# Buzzer_Module.net
KiCad netlist of a schematic drawn in EasyEDA Pro
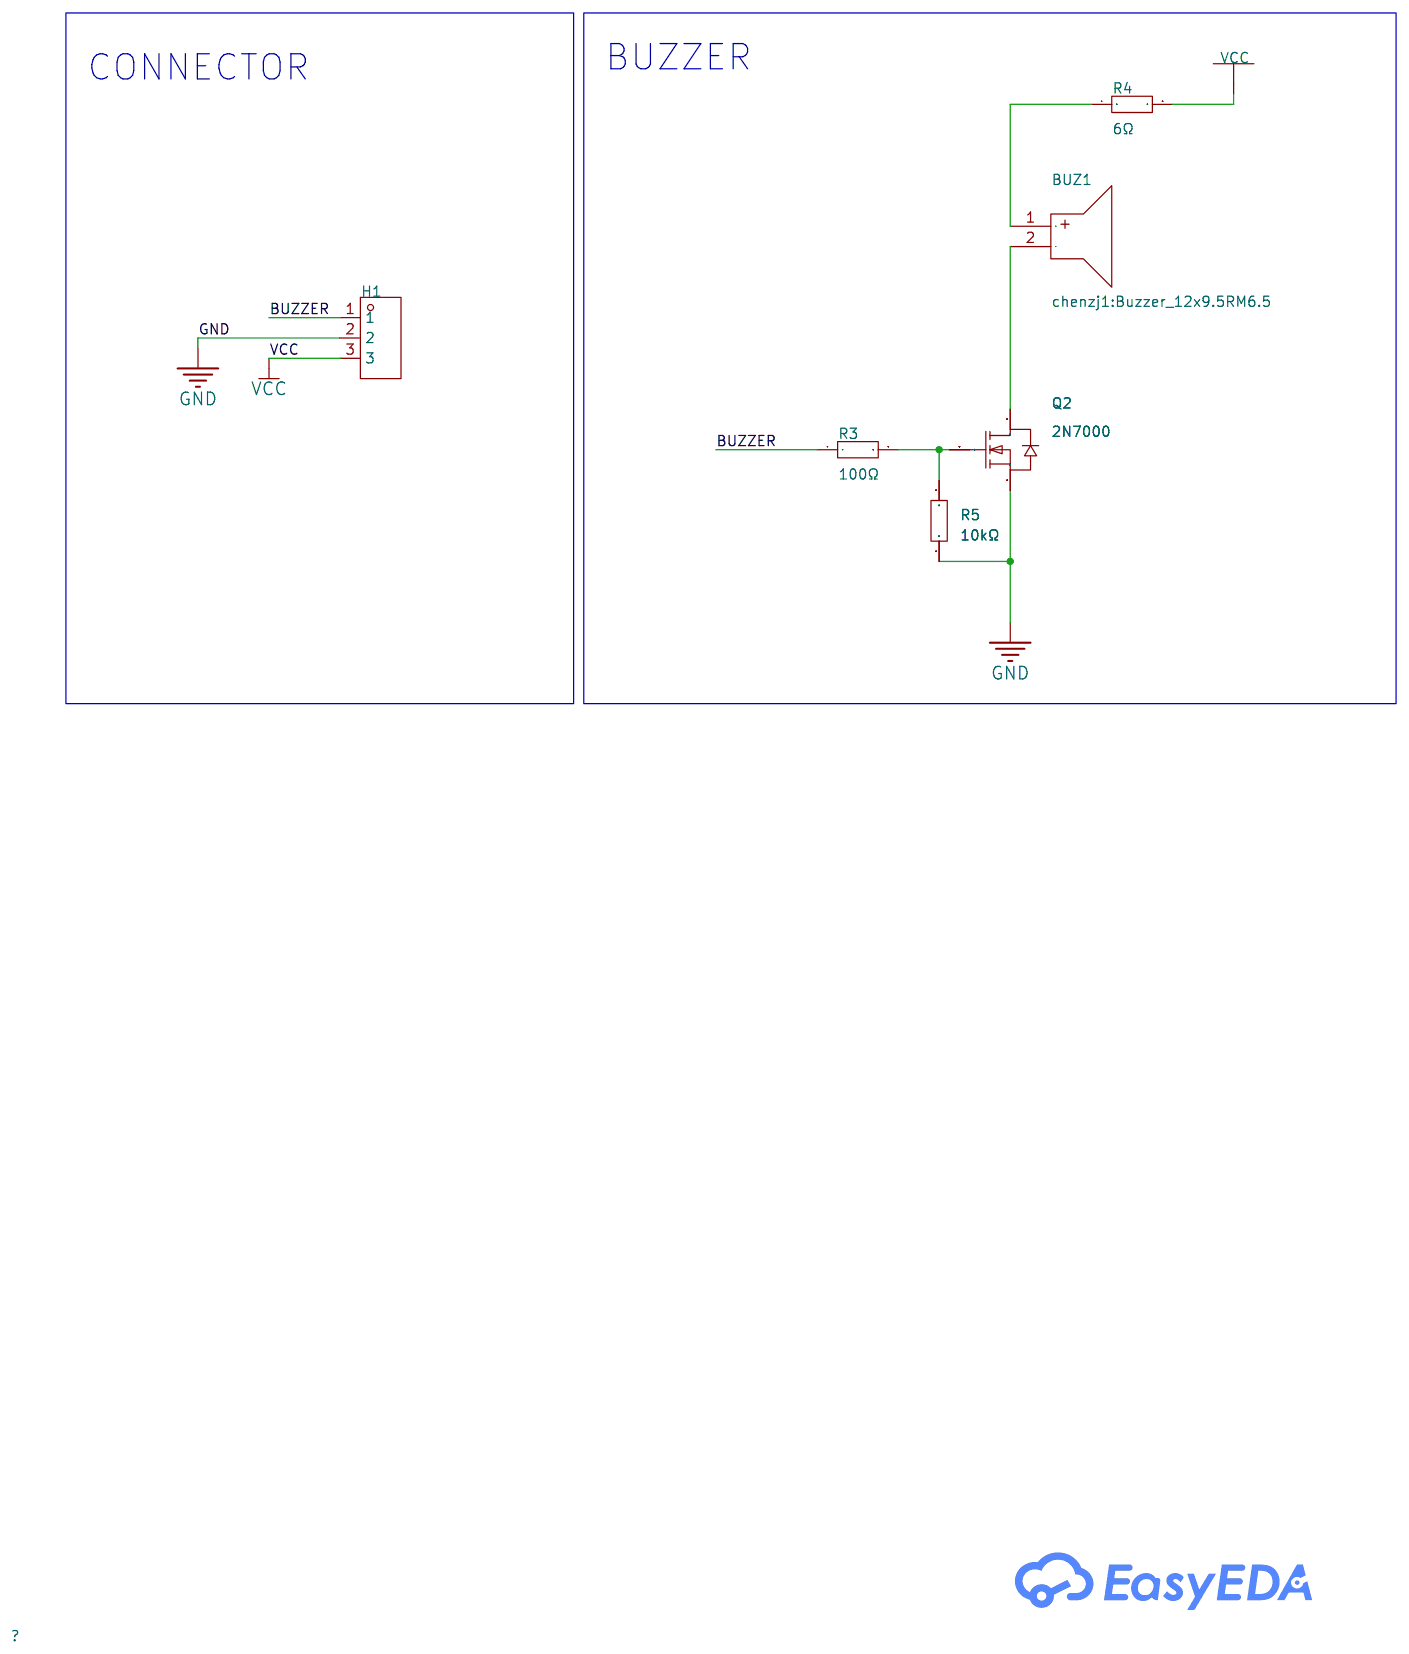
[diagram p0: schematic sheet]

(export (version "E")
  (design (tool "Eeschema 10.0.6"))
  (components
    (comp (ref "BUZ1")
      (value "chenzj1:Buzzer_12x9.5RM6.5")
      (footprint "easyedapro:BUZ-TH_BD12.0-P6.50-D0.6_SEA-1285F")
      (libsource (lib "easyedapro") (part "CHENZJ1{colon}BUZZER_12X9.5RM6.5"))
    )
    (comp (ref "H1")
      (value "~")
      (footprint "easyedapro:HDR-TH_3P-P2.54-V-M")
      (libsource (lib "easyedapro") (part "PZ254V-11-03P_C2937625"))
    )
    (comp (ref "Q2")
      (value "2N7000")
      (footprint "easyedapro:TO-92-3_L4.9-W3.7-P1.27-L")
      (fields (field (name "Manufacturer") "DIOTEC(德欧泰克)"))
      (libsource (lib "easyedapro") (part "2N7000_C3281848"))
    )
    (comp (ref "R3")
      (value "100Ω")
      (footprint "easyedapro:RES-TH_BD1.8-L3.2-P7.20-D0.4")
      (libsource (lib "easyedapro") (part "Res"))
    )
    (comp (ref "R4")
      (value "6Ω")
      (footprint "easyedapro:RES-TH_BD1.8-L3.2-P7.20-D0.4")
      (libsource (lib "easyedapro") (part "Res"))
    )
    (comp (ref "R5")
      (value "10kΩ")
      (footprint "easyedapro:RES-TH_BD1.8-L3.2-P7.20-D0.4")
      (libsource (lib "easyedapro") (part "Res"))
    )
  )
  (nets
    (net (code "1") (name "/BUZZER") (class "Default")
      (node (ref "H1") (pin "1") (pinfunction "1_1") (pintype "unspecified"))
      (node (ref "R3") (pin "1") (pinfunction "1_1") (pintype "input"))
    )
    (net (code "2") (name "GND") (class "Default")
      (node (ref "H1") (pin "2") (pinfunction "2_2") (pintype "unspecified"))
      (node (ref "Q2") (pin "1") (pinfunction "S_1") (pintype "unspecified"))
      (node (ref "R5") (pin "1") (pinfunction "1_1") (pintype "input"))
    )
    (net (code "3") (name "Net-(BUZ1-+)") (class "Default")
      (node (ref "BUZ1") (pin "1") (pinfunction "+_1") (pintype "unspecified"))
      (node (ref "R4") (pin "1") (pinfunction "1_1") (pintype "input"))
    )
    (net (code "4") (name "Net-(BUZ1--)") (class "Default")
      (node (ref "BUZ1") (pin "2") (pinfunction "-_2") (pintype "unspecified"))
      (node (ref "Q2") (pin "3") (pinfunction "D_3") (pintype "unspecified"))
    )
    (net (code "5") (name "Net-(Q2-G)") (class "Default")
      (node (ref "Q2") (pin "2") (pinfunction "G_2") (pintype "unspecified"))
      (node (ref "R3") (pin "2") (pinfunction "2_2") (pintype "input"))
      (node (ref "R5") (pin "2") (pinfunction "2_2") (pintype "input"))
    )
    (net (code "6") (name "VCC") (class "Default")
      (node (ref "H1") (pin "3") (pinfunction "3_3") (pintype "unspecified"))
      (node (ref "R4") (pin "2") (pinfunction "2_2") (pintype "input"))
    )
  )
)
